# LEDBoard.net
KiCad netlist of a schematic drawn in EAGLE
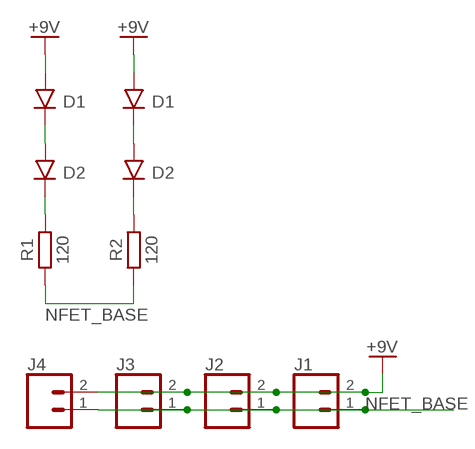
[diagram p0: schematic, sheet 1]

(export (version "E")
  (design (tool "Eeschema 10.0.6"))
  (components
    (comp (ref "D1")
      (value "JB3030")
      (footprint "eagle-import:JB3030")
      (libsource (lib "eagle-import") (part "JB3030"))
    )
    (comp (ref "D2")
      (value "JB3030")
      (footprint "eagle-import:JB3030")
      (libsource (lib "eagle-import") (part "JB3030"))
    )
    (comp (ref "D3")
      (value "JB3030")
      (footprint "eagle-import:JB3030")
      (libsource (lib "eagle-import") (part "JB3030"))
    )
    (comp (ref "D4")
      (value "JB3030")
      (footprint "eagle-import:JB3030")
      (libsource (lib "eagle-import") (part "JB3030"))
    )
    (comp (ref "J1")
      (value "CONN_021X02_NO_SILK")
      (footprint "eagle-import:1X02_NO_SILK")
      (libsource (lib "eagle-import") (part "CONN_021X02_NO_SILK"))
    )
    (comp (ref "J2")
      (value "CONN_021X02_NO_SILK")
      (footprint "eagle-import:1X02_NO_SILK")
      (libsource (lib "eagle-import") (part "CONN_021X02_NO_SILK"))
    )
    (comp (ref "J3")
      (value "CONN_021X02_NO_SILK")
      (footprint "eagle-import:1X02_NO_SILK")
      (libsource (lib "eagle-import") (part "CONN_021X02_NO_SILK"))
    )
    (comp (ref "J4")
      (value "CONN_021X02_NO_SILK")
      (footprint "eagle-import:1X02_NO_SILK")
      (libsource (lib "eagle-import") (part "CONN_021X02_NO_SILK"))
    )
    (comp (ref "R1")
      (value "120")
      (footprint "eagle-import:RESC2012X65")
      (libsource (lib "eagle-import") (part "RCHIP-0805(2012-METRIC)_"))
    )
    (comp (ref "R2")
      (value "120")
      (footprint "eagle-import:RESC2012X65")
      (libsource (lib "eagle-import") (part "RCHIP-0805(2012-METRIC)_"))
    )
  )
  (nets
    (net (code "1") (name "+9V") (class "Default")
      (node (ref "D1") (pin "A") (pinfunction "A_A") (pintype "input"))
      (node (ref "D3") (pin "A") (pinfunction "A_A") (pintype "input"))
      (node (ref "J1") (pin "2") (pinfunction "2_2") (pintype "passive"))
      (node (ref "J2") (pin "2") (pinfunction "2_2") (pintype "passive"))
      (node (ref "J3") (pin "2") (pinfunction "2_2") (pintype "passive"))
      (node (ref "J4") (pin "2") (pinfunction "2_2") (pintype "passive"))
    )
    (net (code "2") (name "/NFET_BASE") (class "Default")
      (node (ref "J1") (pin "1") (pinfunction "1_1") (pintype "passive"))
      (node (ref "J2") (pin "1") (pinfunction "1_1") (pintype "passive"))
      (node (ref "J3") (pin "1") (pinfunction "1_1") (pintype "passive"))
      (node (ref "J4") (pin "1") (pinfunction "1_1") (pintype "passive"))
      (node (ref "R1") (pin "1") (pinfunction "1_1") (pintype "passive"))
      (node (ref "R2") (pin "1") (pinfunction "1_1") (pintype "passive"))
    )
    (net (code "3") (name "Net-(D1-PadC)") (class "Default")
      (node (ref "D1") (pin "C") (pinfunction "C_C") (pintype "output"))
      (node (ref "D2") (pin "A") (pinfunction "A_A") (pintype "input"))
    )
    (net (code "4") (name "Net-(D2-PadC)") (class "Default")
      (node (ref "D2") (pin "C") (pinfunction "C_C") (pintype "output"))
      (node (ref "R1") (pin "2") (pinfunction "2_2") (pintype "passive"))
    )
    (net (code "5") (name "Net-(D3-PadC)") (class "Default")
      (node (ref "D3") (pin "C") (pinfunction "C_C") (pintype "output"))
      (node (ref "D4") (pin "A") (pinfunction "A_A") (pintype "input"))
    )
    (net (code "6") (name "Net-(D4-PadC)") (class "Default")
      (node (ref "D4") (pin "C") (pinfunction "C_C") (pintype "output"))
      (node (ref "R2") (pin "2") (pinfunction "2_2") (pintype "passive"))
    )
  )
)
